# powerSupply.net
KiCad netlist of a schematic drawn in Altium Designer
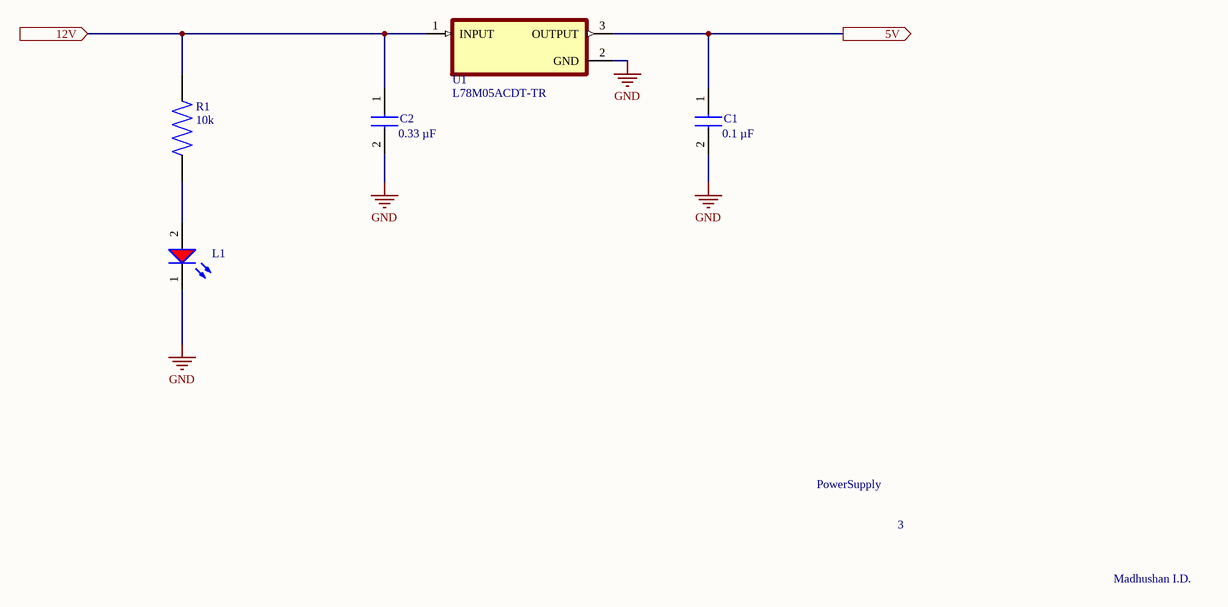
[diagram p0: powerSupply.SchDoc]

(export (version "E")
  (design (tool "Eeschema 10.0.6"))
  (components
    (comp (ref "C1")
      (value "0.1 µF")
      (footprint "SamacSys:C1206")
      (description "Capacitor")
      (fields
        (field (name "MOUSER PART NUMBER") "80-C1206C334K1RECAUT")
        (field (name "ARROW PART NUMBER") "C1206C334K1RECAUTO")
      )
      (libsource (lib "*") (part "C1206C334K1RECAUTO"))
    )
    (comp (ref "C2")
      (value "C1206C334K1RECAUTO")
      (footprint "SamacSys:C1206")
      (description "Capacitor")
      (fields
        (field (name "MANUFACTURER_NAME") "0.33 µF")
        (field (name "MOUSER PART NUMBER") "80-C1206C334K1RECAUT")
      )
      (libsource (lib "*") (part "C1206C334K1RECAUTO"))
    )
    (comp (ref "L1")
      (value "150080SS75000")
      (footprint "WL-SMCW_0805_150080xx75000")
      (libsource (lib "Altium Content Vault") (part "LED_Red_2A-1K"))
    )
    (comp (ref "R1")
      (value "10k")
      (footprint "RES_ERA8AEB103V")
      (fields (field (name "MP") "ERA8AEB103V"))
      (libsource (lib "ERA8AEB103V") (part "ERA8AEB103V"))
    )
    (comp (ref "U1")
      (value "L78M05ACDT-TR")
      (footprint "DPAK228P972X240-4N")
      (description "Linear Voltage Regulator IC 1 Output 500mA DPAK")
      (fields (field (name "MF") "STMicroelectronics"))
      (libsource (lib "L78M05ACDT-TR") (part "L78M05ACDT-TR"))
    )
  )
  (nets
    (net (code "1") (name "/5V") (class "Default")
      (node (ref "C1") (pin "1") (pinfunction "1_1") (pintype "passive"))
      (node (ref "U1") (pin "3") (pinfunction "OUTPUT_3") (pintype "output"))
    )
    (net (code "2") (name "/12V") (class "Default")
      (node (ref "C2") (pin "1") (pinfunction "1_1") (pintype "passive"))
      (node (ref "R1") (pin "2") (pinfunction "2_2") (pintype "passive"))
      (node (ref "U1") (pin "1") (pinfunction "INPUT_1") (pintype "input"))
    )
    (net (code "3") (name "GND") (class "Default")
      (node (ref "C1") (pin "2") (pinfunction "2_2") (pintype "passive"))
      (node (ref "C2") (pin "2") (pinfunction "2_2") (pintype "passive"))
      (node (ref "L1") (pin "1") (pinfunction "K_1") (pintype "passive"))
      (node (ref "U1") (pin "2") (pinfunction "GND_2") (pintype "power_in"))
    )
    (net (code "4") (name "Net-(L1-A)") (class "Default")
      (node (ref "L1") (pin "2") (pinfunction "A_2") (pintype "passive"))
      (node (ref "R1") (pin "1") (pinfunction "1_1") (pintype "passive"))
    )
  )
)
